# 3HP_Multi.net
KiCad netlist of a schematic drawn in EAGLE
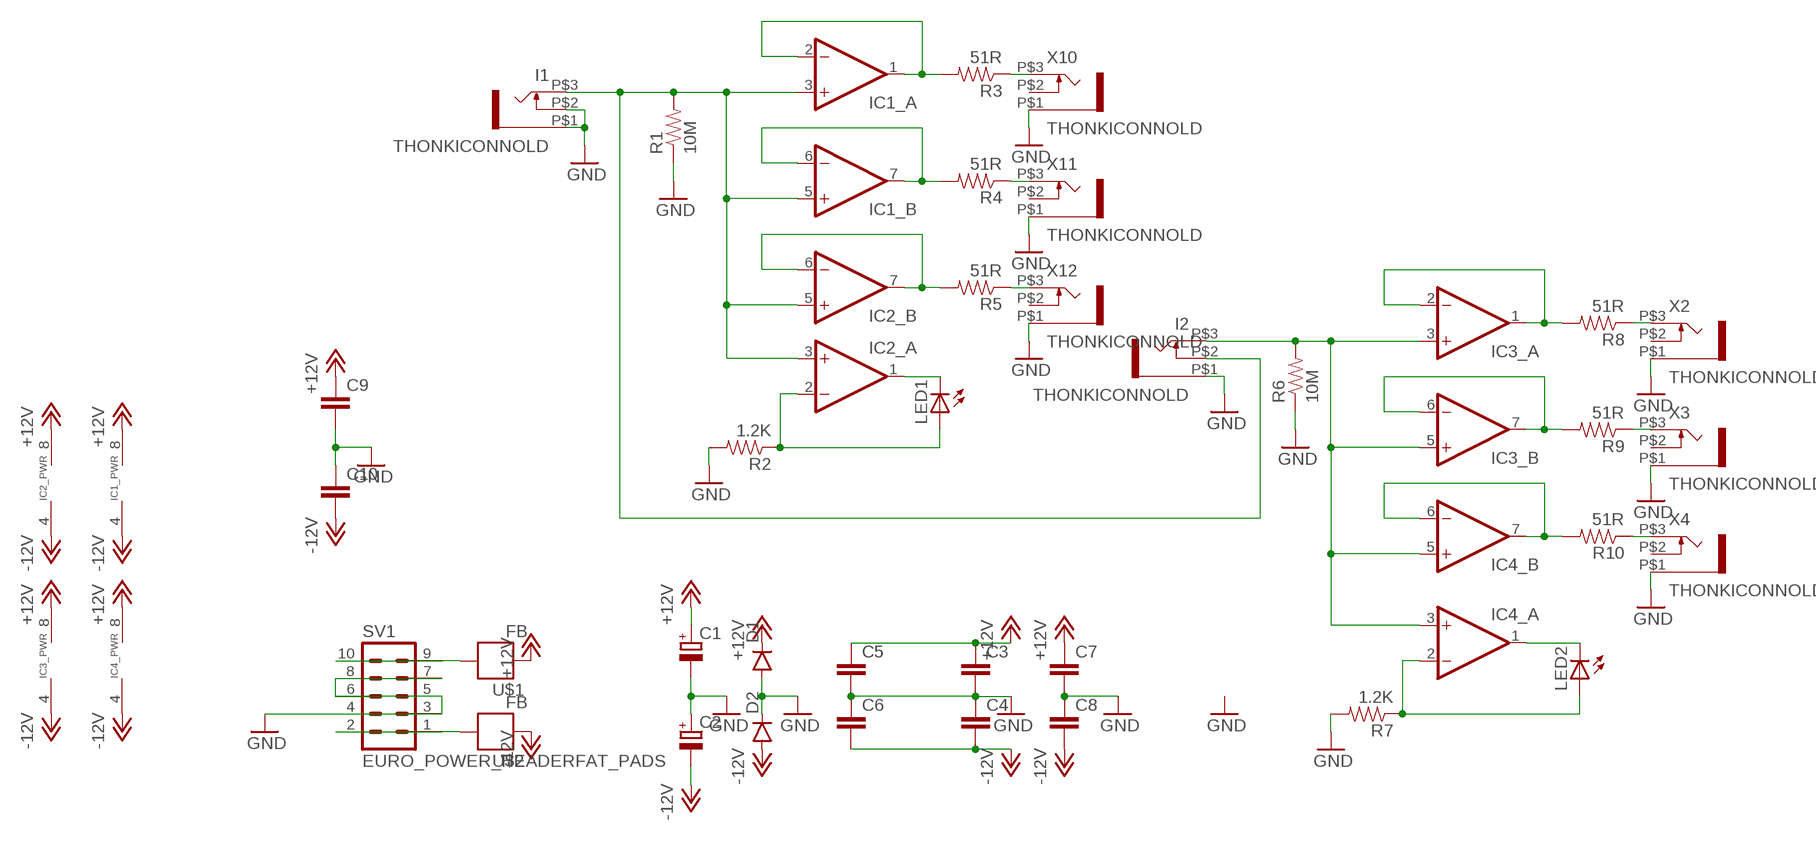
[diagram p0: schematic, sheet 1]

(export (version "E")
  (design (tool "Eeschema 10.0.6"))
  (components
    (comp (ref "C1")
      (value "CAPACITOR_POL-CASE_B")
      (footprint "eagle-import:CASE_B")
      (libsource (lib "eagle-import") (part "CAPACITOR_POL-CASE_B"))
    )
    (comp (ref "C2")
      (value "CAPACITOR_POL-CASE_B")
      (footprint "eagle-import:CASE_B")
      (libsource (lib "eagle-import") (part "CAPACITOR_POL-CASE_B"))
    )
    (comp (ref "C3")
      (value "CAP0603-CAP")
      (footprint "eagle-import:0603-CAP")
      (libsource (lib "eagle-import") (part "CAP0603-CAP"))
    )
    (comp (ref "C4")
      (value "CAP0603-CAP")
      (footprint "eagle-import:0603-CAP")
      (libsource (lib "eagle-import") (part "CAP0603-CAP"))
    )
    (comp (ref "C5")
      (value "CAP0603-CAP")
      (footprint "eagle-import:0603-CAP")
      (libsource (lib "eagle-import") (part "CAP0603-CAP"))
    )
    (comp (ref "C6")
      (value "CAP0603-CAP")
      (footprint "eagle-import:0603-CAP")
      (libsource (lib "eagle-import") (part "CAP0603-CAP"))
    )
    (comp (ref "C7")
      (value "CAP0603-CAP")
      (footprint "eagle-import:0603-CAP")
      (libsource (lib "eagle-import") (part "CAP0603-CAP"))
    )
    (comp (ref "C8")
      (value "CAP0603-CAP")
      (footprint "eagle-import:0603-CAP")
      (libsource (lib "eagle-import") (part "CAP0603-CAP"))
    )
    (comp (ref "C9")
      (value "CAP0603-CAP")
      (footprint "eagle-import:0603-CAP")
      (libsource (lib "eagle-import") (part "CAP0603-CAP"))
    )
    (comp (ref "C10")
      (value "CAP0603-CAP")
      (footprint "eagle-import:0603-CAP")
      (libsource (lib "eagle-import") (part "CAP0603-CAP"))
    )
    (comp (ref "D1")
      (value "DIODESOD123")
      (footprint "eagle-import:SOD-123")
      (libsource (lib "eagle-import") (part "DIODESOD123"))
    )
    (comp (ref "D2")
      (value "DIODESOD123")
      (footprint "eagle-import:SOD-123")
      (libsource (lib "eagle-import") (part "DIODESOD123"))
    )
    (comp (ref "I1")
      (value "THONKICONNOLD")
      (footprint "eagle-import:THONKICONN")
      (libsource (lib "eagle-import") (part "THONKICONNOLD"))
    )
    (comp (ref "I2")
      (value "THONKICONNOLD")
      (footprint "eagle-import:THONKICONN")
      (libsource (lib "eagle-import") (part "THONKICONNOLD"))
    )
    (comp (ref "IC1")
      (value "DUALSMD")
      (footprint "eagle-import:SO08")
      (libsource (lib "eagle-import") (part "DUALSMD"))
    )
    (comp (ref "IC2")
      (value "DUALSMD")
      (footprint "eagle-import:SO08")
      (libsource (lib "eagle-import") (part "DUALSMD"))
    )
    (comp (ref "IC3")
      (value "DUALSMD")
      (footprint "eagle-import:SO08")
      (libsource (lib "eagle-import") (part "DUALSMD"))
    )
    (comp (ref "IC4")
      (value "DUALSMD")
      (footprint "eagle-import:SO08")
      (libsource (lib "eagle-import") (part "DUALSMD"))
    )
    (comp (ref "LED1")
      (value "LED3MM")
      (footprint "eagle-import:LED3MM")
      (libsource (lib "eagle-import") (part "LED3MM"))
    )
    (comp (ref "LED2")
      (value "LED3MM")
      (footprint "eagle-import:LED3MM")
      (libsource (lib "eagle-import") (part "LED3MM"))
    )
    (comp (ref "R1")
      (value "10M")
      (footprint "eagle-import:0603-RES")
      (libsource (lib "eagle-import") (part "RESISTOR0603"))
    )
    (comp (ref "R2")
      (value "1.2K")
      (footprint "eagle-import:0603-RES")
      (libsource (lib "eagle-import") (part "RESISTOR0603"))
    )
    (comp (ref "R3")
      (value "51R")
      (footprint "eagle-import:0603-RES")
      (libsource (lib "eagle-import") (part "RESISTOR0603"))
    )
    (comp (ref "R4")
      (value "51R")
      (footprint "eagle-import:0603-RES")
      (libsource (lib "eagle-import") (part "RESISTOR0603"))
    )
    (comp (ref "R5")
      (value "51R")
      (footprint "eagle-import:0603-RES")
      (libsource (lib "eagle-import") (part "RESISTOR0603"))
    )
    (comp (ref "R6")
      (value "10M")
      (footprint "eagle-import:0603-RES")
      (libsource (lib "eagle-import") (part "RESISTOR0603"))
    )
    (comp (ref "R7")
      (value "1.2K")
      (footprint "eagle-import:0603-RES")
      (libsource (lib "eagle-import") (part "RESISTOR0603"))
    )
    (comp (ref "R8")
      (value "51R")
      (footprint "eagle-import:0603-RES")
      (libsource (lib "eagle-import") (part "RESISTOR0603"))
    )
    (comp (ref "R9")
      (value "51R")
      (footprint "eagle-import:0603-RES")
      (libsource (lib "eagle-import") (part "RESISTOR0603"))
    )
    (comp (ref "R10")
      (value "51R")
      (footprint "eagle-import:0603-RES")
      (libsource (lib "eagle-import") (part "RESISTOR0603"))
    )
    (comp (ref "SV1")
      (value "EURO_POWER_HEADERFAT_PADS")
      (footprint "eagle-import:EURO_PWR_HEADER_FAT")
      (libsource (lib "eagle-import") (part "EURO_POWER_HEADERFAT_PADS"))
    )
    (comp (ref "U$1")
      (value "FB")
      (footprint "eagle-import:0603")
      (libsource (lib "eagle-import") (part "FB"))
    )
    (comp (ref "U$2")
      (value "FB")
      (footprint "eagle-import:0603")
      (libsource (lib "eagle-import") (part "FB"))
    )
    (comp (ref "X2")
      (value "THONKICONNOLD")
      (footprint "eagle-import:THONKICONN")
      (libsource (lib "eagle-import") (part "THONKICONNOLD"))
    )
    (comp (ref "X3")
      (value "THONKICONNOLD")
      (footprint "eagle-import:THONKICONN")
      (libsource (lib "eagle-import") (part "THONKICONNOLD"))
    )
    (comp (ref "X4")
      (value "THONKICONNOLD")
      (footprint "eagle-import:THONKICONN")
      (libsource (lib "eagle-import") (part "THONKICONNOLD"))
    )
    (comp (ref "X10")
      (value "THONKICONNOLD")
      (footprint "eagle-import:THONKICONN")
      (libsource (lib "eagle-import") (part "THONKICONNOLD"))
    )
    (comp (ref "X11")
      (value "THONKICONNOLD")
      (footprint "eagle-import:THONKICONN")
      (libsource (lib "eagle-import") (part "THONKICONNOLD"))
    )
    (comp (ref "X12")
      (value "THONKICONNOLD")
      (footprint "eagle-import:THONKICONN")
      (libsource (lib "eagle-import") (part "THONKICONNOLD"))
    )
  )
  (nets
    (net (code "1") (name "+12V") (class "Default")
      (node (ref "C1") (pin "+") (pinfunction "+_+") (pintype "passive"))
      (node (ref "C3") (pin "1") (pinfunction "1_1") (pintype "passive"))
      (node (ref "C5") (pin "1") (pinfunction "1_1") (pintype "passive"))
      (node (ref "C7") (pin "1") (pinfunction "1_1") (pintype "passive"))
      (node (ref "C9") (pin "1") (pinfunction "1_1") (pintype "passive"))
      (node (ref "D1") (pin "C") (pinfunction "C_C") (pintype "passive"))
      (node (ref "IC1") (pin "8") (pinfunction "V+_8") (pintype "power_in"))
      (node (ref "IC2") (pin "8") (pinfunction "V+_8") (pintype "power_in"))
      (node (ref "IC3") (pin "8") (pinfunction "V+_8") (pintype "power_in"))
      (node (ref "IC4") (pin "8") (pinfunction "V+_8") (pintype "power_in"))
      (node (ref "U$1") (pin "2") (pinfunction "P$2_2") (pintype "bidirectional"))
    )
    (net (code "2") (name "-12V") (class "Default")
      (node (ref "C10") (pin "2") (pinfunction "2_2") (pintype "passive"))
      (node (ref "C2") (pin "-") (pinfunction "-_-") (pintype "passive"))
      (node (ref "C4") (pin "2") (pinfunction "2_2") (pintype "passive"))
      (node (ref "C6") (pin "2") (pinfunction "2_2") (pintype "passive"))
      (node (ref "C8") (pin "2") (pinfunction "2_2") (pintype "passive"))
      (node (ref "D2") (pin "A") (pinfunction "A_A") (pintype "passive"))
      (node (ref "IC1") (pin "4") (pinfunction "V-_4") (pintype "power_in"))
      (node (ref "IC2") (pin "4") (pinfunction "V-_4") (pintype "power_in"))
      (node (ref "IC3") (pin "4") (pinfunction "V-_4") (pintype "power_in"))
      (node (ref "IC4") (pin "4") (pinfunction "V-_4") (pintype "power_in"))
      (node (ref "U$2") (pin "2") (pinfunction "P$2_2") (pintype "bidirectional"))
    )
    (net (code "3") (name "GND") (class "Default")
      (node (ref "C1") (pin "-") (pinfunction "-_-") (pintype "passive"))
      (node (ref "C10") (pin "1") (pinfunction "1_1") (pintype "passive"))
      (node (ref "C2") (pin "+") (pinfunction "+_+") (pintype "passive"))
      (node (ref "C3") (pin "2") (pinfunction "2_2") (pintype "passive"))
      (node (ref "C4") (pin "1") (pinfunction "1_1") (pintype "passive"))
      (node (ref "C5") (pin "2") (pinfunction "2_2") (pintype "passive"))
      (node (ref "C6") (pin "1") (pinfunction "1_1") (pintype "passive"))
      (node (ref "C7") (pin "2") (pinfunction "2_2") (pintype "passive"))
      (node (ref "C8") (pin "1") (pinfunction "1_1") (pintype "passive"))
      (node (ref "C9") (pin "2") (pinfunction "2_2") (pintype "passive"))
      (node (ref "D1") (pin "A") (pinfunction "A_A") (pintype "passive"))
      (node (ref "D2") (pin "C") (pinfunction "C_C") (pintype "passive"))
      (node (ref "I1") (pin "P$1") (pinfunction "5_P$1") (pintype "passive"))
      (node (ref "I1") (pin "P$2") (pinfunction "4_P$2") (pintype "passive"))
      (node (ref "I2") (pin "P$1") (pinfunction "5_P$1") (pintype "passive"))
      (node (ref "R1") (pin "1") (pinfunction "1_1") (pintype "passive"))
      (node (ref "R2") (pin "2") (pinfunction "2_2") (pintype "passive"))
      (node (ref "R6") (pin "1") (pinfunction "1_1") (pintype "passive"))
      (node (ref "R7") (pin "2") (pinfunction "2_2") (pintype "passive"))
      (node (ref "SV1") (pin "3") (pinfunction "3_3") (pintype "passive"))
      (node (ref "SV1") (pin "4") (pinfunction "4_4") (pintype "passive"))
      (node (ref "SV1") (pin "5") (pinfunction "5_5") (pintype "passive"))
      (node (ref "SV1") (pin "6") (pinfunction "6_6") (pintype "passive"))
      (node (ref "SV1") (pin "7") (pinfunction "7_7") (pintype "passive"))
      (node (ref "SV1") (pin "8") (pinfunction "8_8") (pintype "passive"))
      (node (ref "X10") (pin "P$1") (pinfunction "5_P$1") (pintype "passive"))
      (node (ref "X11") (pin "P$1") (pinfunction "5_P$1") (pintype "passive"))
      (node (ref "X12") (pin "P$1") (pinfunction "5_P$1") (pintype "passive"))
      (node (ref "X2") (pin "P$1") (pinfunction "5_P$1") (pintype "passive"))
      (node (ref "X3") (pin "P$1") (pinfunction "5_P$1") (pintype "passive"))
      (node (ref "X4") (pin "P$1") (pinfunction "5_P$1") (pintype "passive"))
    )
    (net (code "4") (name "Net-(I1-3)") (class "Default")
      (node (ref "I1") (pin "P$3") (pinfunction "3_P$3") (pintype "passive"))
      (node (ref "I2") (pin "P$2") (pinfunction "4_P$2") (pintype "passive"))
      (node (ref "IC1") (pin "3") (pinfunction "+IN_3") (pintype "input"))
      (node (ref "IC1") (pin "5") (pinfunction "+IN_5") (pintype "input"))
      (node (ref "IC2") (pin "3") (pinfunction "+IN_3") (pintype "input"))
      (node (ref "IC2") (pin "5") (pinfunction "+IN_5") (pintype "input"))
      (node (ref "R1") (pin "2") (pinfunction "2_2") (pintype "passive"))
    )
    (net (code "5") (name "Net-(I2-3)") (class "Default")
      (node (ref "I2") (pin "P$3") (pinfunction "3_P$3") (pintype "passive"))
      (node (ref "IC3") (pin "3") (pinfunction "+IN_3") (pintype "input"))
      (node (ref "IC3") (pin "5") (pinfunction "+IN_5") (pintype "input"))
      (node (ref "IC4") (pin "3") (pinfunction "+IN_3") (pintype "input"))
      (node (ref "IC4") (pin "5") (pinfunction "+IN_5") (pintype "input"))
      (node (ref "R6") (pin "2") (pinfunction "2_2") (pintype "passive"))
    )
    (net (code "6") (name "Net-(IC1A--IN)") (class "Default")
      (node (ref "IC1") (pin "1") (pinfunction "OUT_1") (pintype "output"))
      (node (ref "IC1") (pin "2") (pinfunction "-IN_2") (pintype "input"))
      (node (ref "R3") (pin "2") (pinfunction "2_2") (pintype "passive"))
    )
    (net (code "7") (name "Net-(IC1B--IN)") (class "Default")
      (node (ref "IC1") (pin "6") (pinfunction "-IN_6") (pintype "input"))
      (node (ref "IC1") (pin "7") (pinfunction "OUT_7") (pintype "output"))
      (node (ref "R4") (pin "2") (pinfunction "2_2") (pintype "passive"))
    )
    (net (code "8") (name "Net-(IC2A--IN)") (class "Default")
      (node (ref "IC2") (pin "2") (pinfunction "-IN_2") (pintype "input"))
      (node (ref "LED1") (pin "A") (pinfunction "A_A") (pintype "passive"))
      (node (ref "R2") (pin "1") (pinfunction "1_1") (pintype "passive"))
    )
    (net (code "9") (name "Net-(IC2A-OUT)") (class "Default")
      (node (ref "IC2") (pin "1") (pinfunction "OUT_1") (pintype "output"))
      (node (ref "LED1") (pin "K") (pinfunction "C_K") (pintype "passive"))
    )
    (net (code "10") (name "Net-(IC2B--IN)") (class "Default")
      (node (ref "IC2") (pin "6") (pinfunction "-IN_6") (pintype "input"))
      (node (ref "IC2") (pin "7") (pinfunction "OUT_7") (pintype "output"))
      (node (ref "R5") (pin "2") (pinfunction "2_2") (pintype "passive"))
    )
    (net (code "11") (name "Net-(IC3A--IN)") (class "Default")
      (node (ref "IC3") (pin "1") (pinfunction "OUT_1") (pintype "output"))
      (node (ref "IC3") (pin "2") (pinfunction "-IN_2") (pintype "input"))
      (node (ref "R8") (pin "2") (pinfunction "2_2") (pintype "passive"))
    )
    (net (code "12") (name "Net-(IC3B--IN)") (class "Default")
      (node (ref "IC3") (pin "6") (pinfunction "-IN_6") (pintype "input"))
      (node (ref "IC3") (pin "7") (pinfunction "OUT_7") (pintype "output"))
      (node (ref "R9") (pin "2") (pinfunction "2_2") (pintype "passive"))
    )
    (net (code "13") (name "Net-(IC4A--IN)") (class "Default")
      (node (ref "IC4") (pin "2") (pinfunction "-IN_2") (pintype "input"))
      (node (ref "LED2") (pin "A") (pinfunction "A_A") (pintype "passive"))
      (node (ref "R7") (pin "1") (pinfunction "1_1") (pintype "passive"))
    )
    (net (code "14") (name "Net-(IC4A-OUT)") (class "Default")
      (node (ref "IC4") (pin "1") (pinfunction "OUT_1") (pintype "output"))
      (node (ref "LED2") (pin "K") (pinfunction "C_K") (pintype "passive"))
    )
    (net (code "15") (name "Net-(IC4B--IN)") (class "Default")
      (node (ref "IC4") (pin "6") (pinfunction "-IN_6") (pintype "input"))
      (node (ref "IC4") (pin "7") (pinfunction "OUT_7") (pintype "output"))
      (node (ref "R10") (pin "2") (pinfunction "2_2") (pintype "passive"))
    )
    (net (code "16") (name "Net-(U$1-P$1)") (class "Default")
      (node (ref "SV1") (pin "10") (pinfunction "10_10") (pintype "passive"))
      (node (ref "SV1") (pin "9") (pinfunction "9_9") (pintype "passive"))
      (node (ref "U$1") (pin "1") (pinfunction "P$1_1") (pintype "bidirectional"))
    )
    (net (code "17") (name "Net-(U$2-P$1)") (class "Default")
      (node (ref "SV1") (pin "1") (pinfunction "1_1") (pintype "passive"))
      (node (ref "SV1") (pin "2") (pinfunction "2_2") (pintype "passive"))
      (node (ref "U$2") (pin "1") (pinfunction "P$1_1") (pintype "bidirectional"))
    )
    (net (code "18") (name "Net-(X2-3)") (class "Default")
      (node (ref "R8") (pin "1") (pinfunction "1_1") (pintype "passive"))
      (node (ref "X2") (pin "P$3") (pinfunction "3_P$3") (pintype "passive"))
    )
    (net (code "19") (name "Net-(X3-3)") (class "Default")
      (node (ref "R9") (pin "1") (pinfunction "1_1") (pintype "passive"))
      (node (ref "X3") (pin "P$3") (pinfunction "3_P$3") (pintype "passive"))
    )
    (net (code "20") (name "Net-(X4-3)") (class "Default")
      (node (ref "R10") (pin "1") (pinfunction "1_1") (pintype "passive"))
      (node (ref "X4") (pin "P$3") (pinfunction "3_P$3") (pintype "passive"))
    )
    (net (code "21") (name "Net-(X10-3)") (class "Default")
      (node (ref "R3") (pin "1") (pinfunction "1_1") (pintype "passive"))
      (node (ref "X10") (pin "P$3") (pinfunction "3_P$3") (pintype "passive"))
    )
    (net (code "22") (name "Net-(X11-3)") (class "Default")
      (node (ref "R4") (pin "1") (pinfunction "1_1") (pintype "passive"))
      (node (ref "X11") (pin "P$3") (pinfunction "3_P$3") (pintype "passive"))
    )
    (net (code "23") (name "Net-(X12-3)") (class "Default")
      (node (ref "R5") (pin "1") (pinfunction "1_1") (pintype "passive"))
      (node (ref "X12") (pin "P$3") (pinfunction "3_P$3") (pintype "passive"))
    )
    (net (code "24") (name "unconnected-(X2-4-PadP$2)") (class "Default")
      (node (ref "X2") (pin "P$2") (pinfunction "4_P$2") (pintype "passive"))
    )
    (net (code "25") (name "unconnected-(X3-4-PadP$2)") (class "Default")
      (node (ref "X3") (pin "P$2") (pinfunction "4_P$2") (pintype "passive"))
    )
    (net (code "26") (name "unconnected-(X4-4-PadP$2)") (class "Default")
      (node (ref "X4") (pin "P$2") (pinfunction "4_P$2") (pintype "passive"))
    )
    (net (code "27") (name "unconnected-(X10-4-PadP$2)") (class "Default")
      (node (ref "X10") (pin "P$2") (pinfunction "4_P$2") (pintype "passive"))
    )
    (net (code "28") (name "unconnected-(X11-4-PadP$2)") (class "Default")
      (node (ref "X11") (pin "P$2") (pinfunction "4_P$2") (pintype "passive"))
    )
    (net (code "29") (name "unconnected-(X12-4-PadP$2)") (class "Default")
      (node (ref "X12") (pin "P$2") (pinfunction "4_P$2") (pintype "passive"))
    )
  )
)
